# 4thLPF.net
KiCad netlist of a schematic drawn in EAGLE
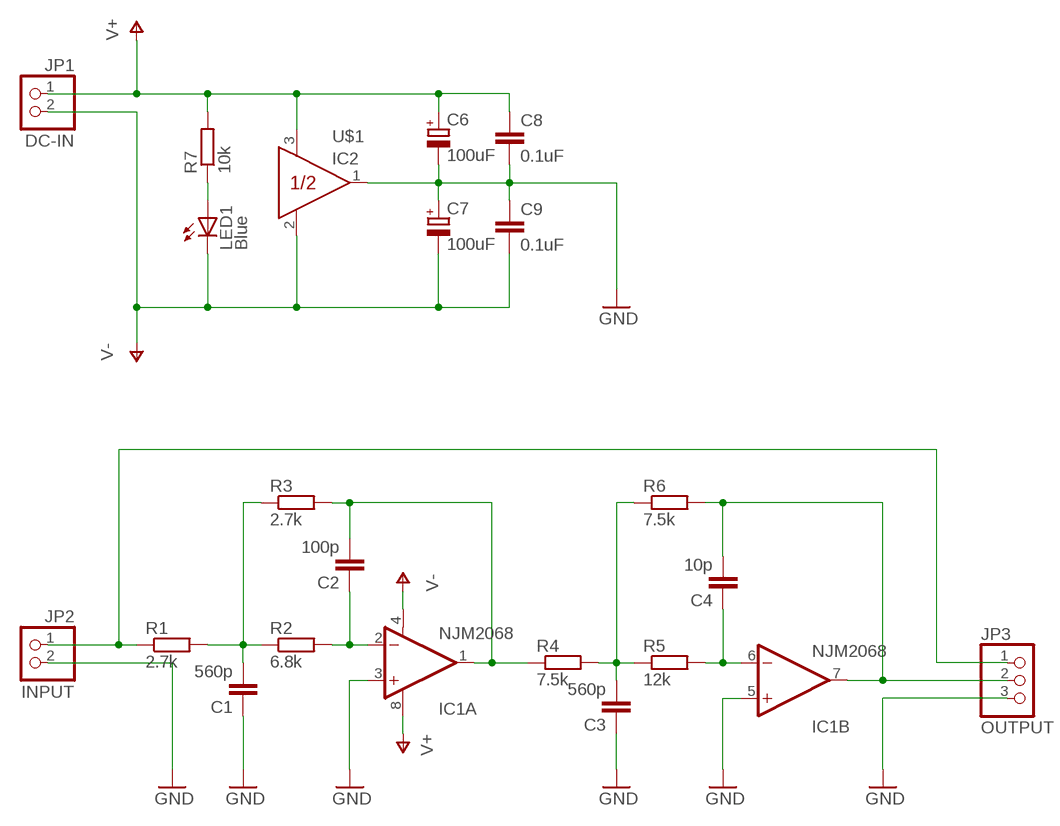
[diagram p0: schematic, sheet 1]

(export (version "E")
  (design (tool "Eeschema 10.0.6"))
  (components
    (comp (ref "C1")
      (value "560p")
      (footprint "eagle-import:C050-035X075")
      (libsource (lib "eagle-import") (part "C-EU050-035X075"))
    )
    (comp (ref "C2")
      (value "100p")
      (footprint "eagle-import:C050-035X075")
      (libsource (lib "eagle-import") (part "C-EU050-035X075"))
    )
    (comp (ref "C3")
      (value "560p")
      (footprint "eagle-import:C050-035X075")
      (libsource (lib "eagle-import") (part "C-EU050-035X075"))
    )
    (comp (ref "C4")
      (value "10p")
      (footprint "eagle-import:C050-024X044")
      (libsource (lib "eagle-import") (part "C-EU050-024X044"))
    )
    (comp (ref "C6")
      (value "100uF")
      (footprint "eagle-import:E2,5-6")
      (libsource (lib "eagle-import") (part "CPOL-EUE2.5-6"))
    )
    (comp (ref "C7")
      (value "100uF")
      (footprint "eagle-import:E2,5-6")
      (libsource (lib "eagle-import") (part "CPOL-EUE2.5-6"))
    )
    (comp (ref "C8")
      (value "0.1uF")
      (footprint "eagle-import:C050-024X044")
      (libsource (lib "eagle-import") (part "C-EU050-024X044"))
    )
    (comp (ref "C9")
      (value "0.1uF")
      (footprint "eagle-import:C025-024X044")
      (libsource (lib "eagle-import") (part "C-EU025-024X044"))
    )
    (comp (ref "IC1")
      (value "NJM2068")
      (footprint "eagle-import:DIL08")
      (fields (field (name "MF") "TEXAS INSTRUMENTS") (field (name "MPN") "OPA2134PA"))
      (libsource (lib "eagle-import") (part "OPA2134P"))
    )
    (comp (ref "JP1")
      (value "DC-IN")
      (footprint "eagle-import:1X02")
      (libsource (lib "eagle-import") (part "PINHD-1X2"))
    )
    (comp (ref "JP2")
      (value "INPUT")
      (footprint "eagle-import:1X02")
      (libsource (lib "eagle-import") (part "PINHD-1X2"))
    )
    (comp (ref "JP3")
      (value "OUTPUT")
      (footprint "eagle-import:1X03")
      (libsource (lib "eagle-import") (part "PINHD-1X3"))
    )
    (comp (ref "LED1")
      (value "Blue")
      (footprint "eagle-import:LED3MM")
      (libsource (lib "eagle-import") (part "LED3MM"))
    )
    (comp (ref "R1")
      (value "2.7k")
      (footprint "eagle-import:0207_7")
      (libsource (lib "eagle-import") (part "R-EU_0207/7"))
    )
    (comp (ref "R2")
      (value "6.8k")
      (footprint "eagle-import:0207_7")
      (libsource (lib "eagle-import") (part "R-EU_0207/7"))
    )
    (comp (ref "R3")
      (value "2.7k")
      (footprint "eagle-import:0207_7")
      (libsource (lib "eagle-import") (part "R-EU_0207/7"))
    )
    (comp (ref "R4")
      (value "7.5k")
      (footprint "eagle-import:0207_7")
      (libsource (lib "eagle-import") (part "R-EU_0207/7"))
    )
    (comp (ref "R5")
      (value "12k")
      (footprint "eagle-import:0207_7")
      (libsource (lib "eagle-import") (part "R-EU_0207/7"))
    )
    (comp (ref "R6")
      (value "7.5k")
      (footprint "eagle-import:0207_7")
      (libsource (lib "eagle-import") (part "R-EU_0207/7"))
    )
    (comp (ref "R7")
      (value "10k")
      (footprint "eagle-import:0207_7")
      (libsource (lib "eagle-import") (part "R-EU_0207/7"))
    )
    (comp (ref "U$1")
      (value "IC2")
      (footprint "eagle-import:TO226AA")
      (libsource (lib "eagle-import") (part "TLE2426LPC"))
    )
  )
  (nets
    (net (code "1") (name "GND") (class "Default")
      (node (ref "C1") (pin "1") (pinfunction "1_1") (pintype "passive"))
      (node (ref "C3") (pin "1") (pinfunction "1_1") (pintype "passive"))
      (node (ref "C6") (pin "-") (pinfunction "-_-") (pintype "passive"))
      (node (ref "C7") (pin "+") (pinfunction "+_+") (pintype "passive"))
      (node (ref "C8") (pin "2") (pinfunction "2_2") (pintype "passive"))
      (node (ref "C9") (pin "1") (pinfunction "1_1") (pintype "passive"))
      (node (ref "IC1") (pin "3") (pinfunction "+IN_3") (pintype "input"))
      (node (ref "IC1") (pin "5") (pinfunction "+IN_5") (pintype "input"))
      (node (ref "JP2") (pin "2") (pinfunction "2_2") (pintype "passive"))
      (node (ref "JP3") (pin "3") (pinfunction "3_3") (pintype "passive"))
      (node (ref "U$1") (pin "1") (pinfunction "OUT_1") (pintype "passive"))
    )
    (net (code "2") (name "Net-(C1-Pad2)") (class "Default")
      (node (ref "C1") (pin "2") (pinfunction "2_2") (pintype "passive"))
      (node (ref "R1") (pin "2") (pinfunction "2_2") (pintype "passive"))
      (node (ref "R2") (pin "1") (pinfunction "1_1") (pintype "passive"))
      (node (ref "R3") (pin "1") (pinfunction "1_1") (pintype "passive"))
    )
    (net (code "3") (name "Net-(C3-Pad2)") (class "Default")
      (node (ref "C3") (pin "2") (pinfunction "2_2") (pintype "passive"))
      (node (ref "R4") (pin "2") (pinfunction "2_2") (pintype "passive"))
      (node (ref "R5") (pin "1") (pinfunction "1_1") (pintype "passive"))
      (node (ref "R6") (pin "1") (pinfunction "1_1") (pintype "passive"))
    )
    (net (code "4") (name "Net-(IC1A--IN)") (class "Default")
      (node (ref "C2") (pin "1") (pinfunction "1_1") (pintype "passive"))
      (node (ref "IC1") (pin "2") (pinfunction "-IN_2") (pintype "input"))
      (node (ref "R2") (pin "2") (pinfunction "2_2") (pintype "passive"))
    )
    (net (code "5") (name "Net-(IC1A-OUT)") (class "Default")
      (node (ref "C2") (pin "2") (pinfunction "2_2") (pintype "passive"))
      (node (ref "IC1") (pin "1") (pinfunction "OUT_1") (pintype "output"))
      (node (ref "R3") (pin "2") (pinfunction "2_2") (pintype "passive"))
      (node (ref "R4") (pin "1") (pinfunction "1_1") (pintype "passive"))
    )
    (net (code "6") (name "Net-(IC1B--IN)") (class "Default")
      (node (ref "C4") (pin "1") (pinfunction "1_1") (pintype "passive"))
      (node (ref "IC1") (pin "6") (pinfunction "-IN_6") (pintype "input"))
      (node (ref "R5") (pin "2") (pinfunction "2_2") (pintype "passive"))
    )
    (net (code "7") (name "Net-(IC1B-OUT)") (class "Default")
      (node (ref "C4") (pin "2") (pinfunction "2_2") (pintype "passive"))
      (node (ref "IC1") (pin "7") (pinfunction "OUT_7") (pintype "output"))
      (node (ref "JP3") (pin "2") (pinfunction "2_2") (pintype "passive"))
      (node (ref "R6") (pin "2") (pinfunction "2_2") (pintype "passive"))
    )
    (net (code "8") (name "Net-(JP2-Pad1)") (class "Default")
      (node (ref "JP2") (pin "1") (pinfunction "1_1") (pintype "passive"))
      (node (ref "JP3") (pin "1") (pinfunction "1_1") (pintype "passive"))
      (node (ref "R1") (pin "1") (pinfunction "1_1") (pintype "passive"))
    )
    (net (code "9") (name "Net-(LED1-PadA)") (class "Default")
      (node (ref "LED1") (pin "A") (pinfunction "A_A") (pintype "passive"))
      (node (ref "R7") (pin "1") (pinfunction "1_1") (pintype "passive"))
    )
    (net (code "10") (name "V+") (class "Default")
      (node (ref "C6") (pin "+") (pinfunction "+_+") (pintype "passive"))
      (node (ref "C8") (pin "1") (pinfunction "1_1") (pintype "passive"))
      (node (ref "IC1") (pin "8") (pinfunction "V+_8") (pintype "power_in"))
      (node (ref "JP1") (pin "1") (pinfunction "1_1") (pintype "passive"))
      (node (ref "R7") (pin "2") (pinfunction "2_2") (pintype "passive"))
      (node (ref "U$1") (pin "3") (pinfunction "IN_3") (pintype "passive"))
    )
    (net (code "11") (name "V-") (class "Default")
      (node (ref "C7") (pin "-") (pinfunction "-_-") (pintype "passive"))
      (node (ref "C9") (pin "2") (pinfunction "2_2") (pintype "passive"))
      (node (ref "IC1") (pin "4") (pinfunction "V-_4") (pintype "power_in"))
      (node (ref "JP1") (pin "2") (pinfunction "2_2") (pintype "passive"))
      (node (ref "LED1") (pin "K") (pinfunction "C_K") (pintype "passive"))
      (node (ref "U$1") (pin "2") (pinfunction "COM_2") (pintype "passive"))
    )
  )
)
